# 03_-_ETHERNET.net
KiCad netlist of a schematic drawn in Altium Designer
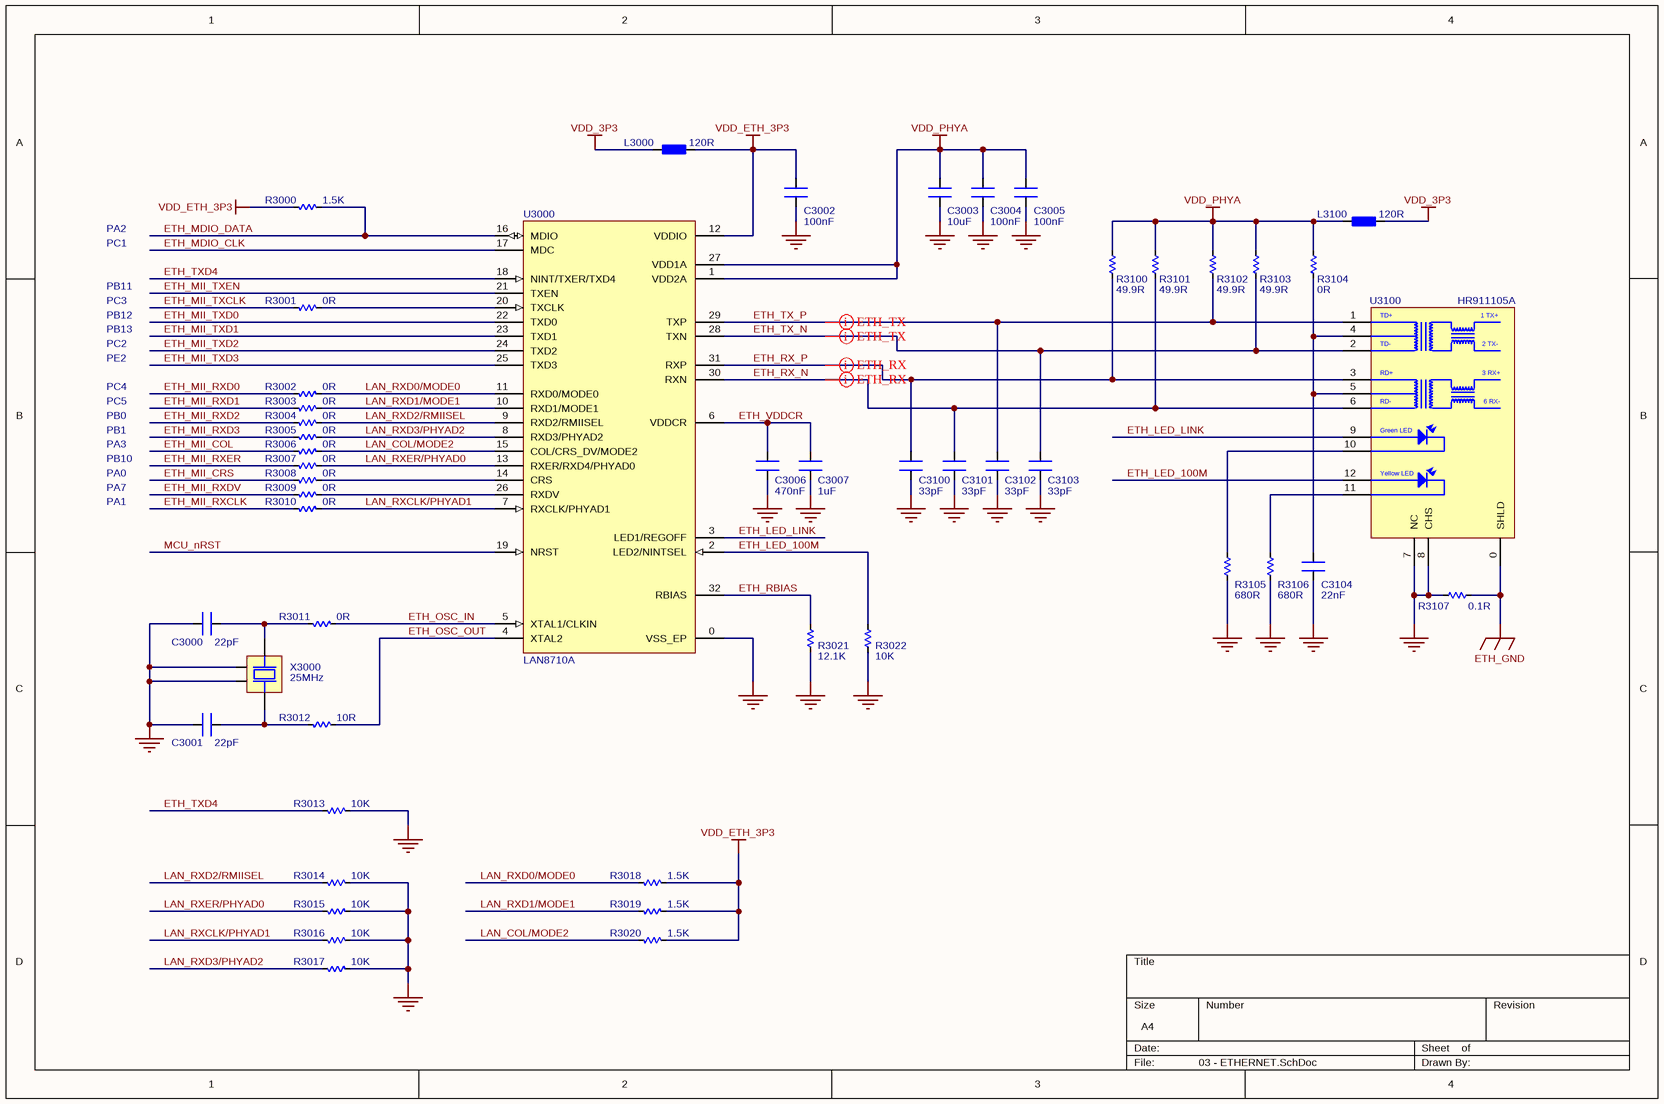
[diagram p0: 03 - ETHERNET.SchDoc]

(export (version "E")
  (design (tool "Eeschema 10.0.6"))
  (components
    (comp (ref "C3000")
      (value "22pF")
      (footprint "CN-SMD-0402")
      (description "Ceramic Capacitor SMD 0402 22pF ±20% 50V")
      (fields (field (name "Comment") "Capacitor"))
      (libsource (lib "AS50") (part "Cap"))
    )
    (comp (ref "C3001")
      (value "22pF")
      (footprint "CN-SMD-0402")
      (description "Ceramic Capacitor SMD 0402 22pF ±20% 50V")
      (fields (field (name "Comment") "Capacitor"))
      (libsource (lib "AS50") (part "Cap"))
    )
    (comp (ref "C3002")
      (value "100nF")
      (footprint "CN-SMD-0402")
      (description "Ceramic Capacitor SMD 0402 100nF ±20% 16V")
      (fields (field (name "Comment") "Capacitor"))
      (libsource (lib "AS50") (part "Cap"))
    )
    (comp (ref "C3003")
      (value "10uF")
      (footprint "CN-SMD-0603")
      (description "Ceramic Capacitor SMD 0603 10uF ±20% 10V")
      (fields (field (name "Comment") "Capacitor"))
      (libsource (lib "AS50") (part "Cap"))
    )
    (comp (ref "C3004")
      (value "100nF")
      (footprint "CN-SMD-0402")
      (description "Ceramic Capacitor SMD 0402 100nF ±20% 16V")
      (fields (field (name "Comment") "Capacitor"))
      (libsource (lib "AS50") (part "Cap"))
    )
    (comp (ref "C3005")
      (value "100nF")
      (footprint "CN-SMD-0402")
      (description "Ceramic Capacitor SMD 0402 100nF ±20% 16V")
      (fields (field (name "Comment") "Capacitor"))
      (libsource (lib "AS50") (part "Cap"))
    )
    (comp (ref "C3006")
      (value "470nF")
      (footprint "CN-SMD-0402")
      (description "Ceramic Capacitor SMD 0402 470nF ±20% 10V")
      (fields (field (name "Comment") "Capacitor"))
      (libsource (lib "AS50") (part "Cap"))
    )
    (comp (ref "C3007")
      (value "1uF")
      (footprint "CN-SMD-0603")
      (description "Ceramic Capacitor SMD 0603 1uF ±20% 50V")
      (fields (field (name "Comment") "Capacitor"))
      (libsource (lib "AS50") (part "Cap"))
    )
    (comp (ref "C3100")
      (value "33pF")
      (footprint "CN-SMD-0402")
      (description "Ceramic Capacitor SMD 0402 33pF ±20% 50V")
      (fields (field (name "Comment") "Capacitor"))
      (libsource (lib "AS50") (part "Cap"))
    )
    (comp (ref "C3101")
      (value "33pF")
      (footprint "CN-SMD-0402")
      (description "Ceramic Capacitor SMD 0402 33pF ±20% 50V")
      (fields (field (name "Comment") "Capacitor"))
      (libsource (lib "AS50") (part "Cap"))
    )
    (comp (ref "C3102")
      (value "33pF")
      (footprint "CN-SMD-0402")
      (description "Ceramic Capacitor SMD 0402 33pF ±20% 50V")
      (fields (field (name "Comment") "Capacitor"))
      (libsource (lib "AS50") (part "Cap"))
    )
    (comp (ref "C3103")
      (value "33pF")
      (footprint "CN-SMD-0402")
      (description "Ceramic Capacitor SMD 0402 33pF ±20% 50V")
      (fields (field (name "Comment") "Capacitor"))
      (libsource (lib "AS50") (part "Cap"))
    )
    (comp (ref "C3104")
      (value "22nF")
      (footprint "CN-SMD-0402")
      (description "Ceramic Capacitor SMD 0402 22nF ±20% 50V")
      (fields (field (name "Comment") "Capacitor"))
      (libsource (lib "AS50") (part "Cap"))
    )
    (comp (ref "L3000")
      (value "120R")
      (footprint "L-SMD-0603")
      (description "Ferrite bead SMD 0603 120 Ohm @100MHz")
      (fields (field (name "Comment") "Ferrite bead"))
      (libsource (lib "AS50") (part "Ferrite bead"))
    )
    (comp (ref "L3100")
      (value "120R")
      (footprint "L-SMD-0603")
      (description "Ferrite bead SMD 0603 120 Ohm @100MHz")
      (fields (field (name "Comment") "Ferrite bead"))
      (libsource (lib "AS50") (part "Ferrite bead"))
    )
    (comp (ref "R3000")
      (value "1.5K")
      (footprint "RES-SMD-0402")
      (description "Resistor SMD 0402 1.5K 1% 0.063W")
      (fields (field (name "Comment") "Resistor"))
      (libsource (lib "AS50") (part "Res"))
    )
    (comp (ref "R3001")
      (value "0R")
      (footprint "RES-SMD-0402")
      (description "Resistor SMD 0402 0R 1% 0.063W")
      (fields (field (name "Comment") "Resistor"))
      (libsource (lib "AS50") (part "Res"))
    )
    (comp (ref "R3002")
      (value "0R")
      (footprint "RES-SMD-0402")
      (description "Resistor SMD 0402 0R 1% 0.063W")
      (fields (field (name "Comment") "Resistor"))
      (libsource (lib "AS50") (part "Res"))
    )
    (comp (ref "R3003")
      (value "0R")
      (footprint "RES-SMD-0402")
      (description "Resistor SMD 0402 0R 1% 0.063W")
      (fields (field (name "Comment") "Resistor"))
      (libsource (lib "AS50") (part "Res"))
    )
    (comp (ref "R3004")
      (value "0R")
      (footprint "RES-SMD-0402")
      (description "Resistor SMD 0402 0R 1% 0.063W")
      (fields (field (name "Comment") "Resistor"))
      (libsource (lib "AS50") (part "Res"))
    )
    (comp (ref "R3005")
      (value "0R")
      (footprint "RES-SMD-0402")
      (description "Resistor SMD 0402 0R 1% 0.063W")
      (fields (field (name "Comment") "Resistor"))
      (libsource (lib "AS50") (part "Res"))
    )
    (comp (ref "R3006")
      (value "0R")
      (footprint "RES-SMD-0402")
      (description "Resistor SMD 0402 0R 1% 0.063W")
      (fields (field (name "Comment") "Resistor"))
      (libsource (lib "AS50") (part "Res"))
    )
    (comp (ref "R3007")
      (value "0R")
      (footprint "RES-SMD-0402")
      (description "Resistor SMD 0402 0R 1% 0.063W")
      (fields (field (name "Comment") "Resistor"))
      (libsource (lib "AS50") (part "Res"))
    )
    (comp (ref "R3008")
      (value "0R")
      (footprint "RES-SMD-0402")
      (description "Resistor SMD 0402 0R 1% 0.063W")
      (fields (field (name "Comment") "Resistor"))
      (libsource (lib "AS50") (part "Res"))
    )
    (comp (ref "R3009")
      (value "0R")
      (footprint "RES-SMD-0402")
      (description "Resistor SMD 0402 0R 1% 0.063W")
      (fields (field (name "Comment") "Resistor"))
      (libsource (lib "AS50") (part "Res"))
    )
    (comp (ref "R3010")
      (value "0R")
      (footprint "RES-SMD-0402")
      (description "Resistor SMD 0402 0R 1% 0.063W")
      (fields (field (name "Comment") "Resistor"))
      (libsource (lib "AS50") (part "Res"))
    )
    (comp (ref "R3011")
      (value "0R")
      (footprint "RES-SMD-0402")
      (description "Resistor SMD 0402 0R 1% 0.063W")
      (fields (field (name "Comment") "Resistor"))
      (libsource (lib "AS50") (part "Res"))
    )
    (comp (ref "R3012")
      (value "10R")
      (footprint "RES-SMD-0402")
      (description "Resistor SMD 0402 10R 1% 0.063W")
      (fields (field (name "Comment") "Resistor"))
      (libsource (lib "AS50") (part "Res"))
    )
    (comp (ref "R3013")
      (value "10K")
      (footprint "RES-SMD-0402")
      (description "Resistor SMD 0402 10K 1% 0.063W")
      (fields (field (name "Comment") "Resistor"))
      (libsource (lib "AS50") (part "Res"))
    )
    (comp (ref "R3014")
      (value "10K")
      (footprint "RES-SMD-0402")
      (description "Resistor SMD 0402 10K 1% 0.063W")
      (fields (field (name "Comment") "Resistor"))
      (libsource (lib "AS50") (part "Res"))
    )
    (comp (ref "R3015")
      (value "10K")
      (footprint "RES-SMD-0402")
      (description "Resistor SMD 0402 10K 1% 0.063W")
      (fields (field (name "Comment") "Resistor"))
      (libsource (lib "AS50") (part "Res"))
    )
    (comp (ref "R3016")
      (value "10K")
      (footprint "RES-SMD-0402")
      (description "Resistor SMD 0402 10K 1% 0.063W")
      (fields (field (name "Comment") "Resistor"))
      (libsource (lib "AS50") (part "Res"))
    )
    (comp (ref "R3017")
      (value "10K")
      (footprint "RES-SMD-0402")
      (description "Resistor SMD 0402 10K 1% 0.063W")
      (fields (field (name "Comment") "Resistor"))
      (libsource (lib "AS50") (part "Res"))
    )
    (comp (ref "R3018")
      (value "1.5K")
      (footprint "RES-SMD-0402")
      (description "Resistor SMD 0402 1.5K 1% 0.063W")
      (fields (field (name "Comment") "Resistor"))
      (libsource (lib "AS50") (part "Res"))
    )
    (comp (ref "R3019")
      (value "1.5K")
      (footprint "RES-SMD-0402")
      (description "Resistor SMD 0402 1.5K 1% 0.063W")
      (fields (field (name "Comment") "Resistor"))
      (libsource (lib "AS50") (part "Res"))
    )
    (comp (ref "R3020")
      (value "1.5K")
      (footprint "RES-SMD-0402")
      (description "Resistor SMD 0402 1.5K 1% 0.063W")
      (fields (field (name "Comment") "Resistor"))
      (libsource (lib "AS50") (part "Res"))
    )
    (comp (ref "R3021")
      (value "12.1K")
      (footprint "RES-SMD-0402")
      (description "Resistor SMD 0402 12.1K 1% 0.063W")
      (fields (field (name "Comment") "Resistor"))
      (libsource (lib "AS50") (part "Res"))
    )
    (comp (ref "R3022")
      (value "10K")
      (footprint "RES-SMD-0402")
      (description "Resistor SMD 0402 10K 1% 0.063W")
      (fields (field (name "Comment") "Resistor"))
      (libsource (lib "AS50") (part "Res"))
    )
    (comp (ref "R3100")
      (value "49.9R")
      (footprint "RES-SMD-0402")
      (description "Resistor SMD 0402 49.9R 1% 0.063W")
      (fields (field (name "Comment") "Resistor"))
      (libsource (lib "AS50") (part "Res"))
    )
    (comp (ref "R3101")
      (value "49.9R")
      (footprint "RES-SMD-0402")
      (description "Resistor SMD 0402 49.9R 1% 0.063W")
      (fields (field (name "Comment") "Resistor"))
      (libsource (lib "AS50") (part "Res"))
    )
    (comp (ref "R3102")
      (value "49.9R")
      (footprint "RES-SMD-0402")
      (description "Resistor SMD 0402 49.9R 1% 0.063W")
      (fields (field (name "Comment") "Resistor"))
      (libsource (lib "AS50") (part "Res"))
    )
    (comp (ref "R3103")
      (value "49.9R")
      (footprint "RES-SMD-0402")
      (description "Resistor SMD 0402 49.9R 1% 0.063W")
      (fields (field (name "Comment") "Resistor"))
      (libsource (lib "AS50") (part "Res"))
    )
    (comp (ref "R3104")
      (value "0R")
      (footprint "RES-SMD-0402")
      (description "Resistor SMD 0402 0R 1% 0.063W")
      (fields (field (name "Comment") "Resistor"))
      (libsource (lib "AS50") (part "Res"))
    )
    (comp (ref "R3105")
      (value "680R")
      (footprint "RES-SMD-0402")
      (description "Resistor SMD 0402 680R 1% 0.063W")
      (fields (field (name "Comment") "Resistor"))
      (libsource (lib "AS50") (part "Res"))
    )
    (comp (ref "R3106")
      (value "680R")
      (footprint "RES-SMD-0402")
      (description "Resistor SMD 0402 680R 1% 0.063W")
      (fields (field (name "Comment") "Resistor"))
      (libsource (lib "AS50") (part "Res"))
    )
    (comp (ref "R3107")
      (value "0.1R")
      (footprint "RES-SMD-1206")
      (description "Resistor SMD 1206 0.1R 1% 0.25W")
      (fields (field (name "Comment") "Resistor"))
      (libsource (lib "AS50") (part "Res"))
    )
    (comp (ref "U3000")
      (value "LAN8710A")
      (footprint "IC:QFN50P500X500X100-33N-D")
      (description "Microchip MII/RMII 10/100 Ethernet Transceiver\r\nwith HP Auto-MDIX and flexPWR® Technology")
      (fields
        (field (name "MANUFACTURER_PART_NUMBER") "LAN8710AI-EZK")
        (field (name "MOUSER PART NUMBER") "886-LAN8710AI-EZK")
      )
      (libsource (lib "AS50") (part "LAN8710A"))
    )
    (comp (ref "U3100")
      (value "HR911105A")
      (footprint "RJ-45_HR911105A")
      (libsource (lib "AS50") (part "HR911105A"))
    )
    (comp (ref "X3000")
      (value "25MHz")
      (footprint "XT-SMD-3225-4P")
      (description "Crystal Oscillator SMD-3225 25MHz 4-pin")
      (fields (field (name "Comment") "Crystal"))
      (libsource (lib "AS50") (part "XT4"))
    )
  )
  (nets
    (net (code "1") (name "/ETH_LED_100M") (class "Default")
      (node (ref "R3022") (pin "1") (pinfunction "1_1") (pintype "passive"))
      (node (ref "U3000") (pin "2") (pinfunction "LED2/NINTSEL_2") (pintype "input"))
      (node (ref "U3100") (pin "12") (pinfunction "Yellow+_12") (pintype "passive"))
    )
    (net (code "2") (name "/ETH_LED_LINK") (class "Default")
      (node (ref "U3000") (pin "3") (pinfunction "LED1/REGOFF_3") (pintype "passive"))
      (node (ref "U3100") (pin "9") (pinfunction "Green+_9") (pintype "passive"))
    )
    (net (code "3") (name "/ETH_MDIO_CLK") (class "Default")
      (node (ref "U3000") (pin "17") (pinfunction "MDC_17") (pintype "passive"))
    )
    (net (code "4") (name "/ETH_MDIO_DATA") (class "Default")
      (node (ref "R3000") (pin "1") (pinfunction "1_1") (pintype "passive"))
      (node (ref "U3000") (pin "16") (pinfunction "MDIO_16") (pintype "bidirectional"))
    )
    (net (code "5") (name "/ETH_MII_COL") (class "Default")
      (node (ref "R3006") (pin "2") (pinfunction "2_2") (pintype "passive"))
    )
    (net (code "6") (name "/ETH_MII_CRS") (class "Default")
      (node (ref "R3008") (pin "2") (pinfunction "2_2") (pintype "passive"))
    )
    (net (code "7") (name "/ETH_MII_RXCLK") (class "Default")
      (node (ref "R3010") (pin "2") (pinfunction "2_2") (pintype "passive"))
    )
    (net (code "8") (name "/ETH_MII_RXD0") (class "Default")
      (node (ref "R3002") (pin "2") (pinfunction "2_2") (pintype "passive"))
    )
    (net (code "9") (name "/ETH_MII_RXD1") (class "Default")
      (node (ref "R3003") (pin "2") (pinfunction "2_2") (pintype "passive"))
    )
    (net (code "10") (name "/ETH_MII_RXD2") (class "Default")
      (node (ref "R3004") (pin "2") (pinfunction "2_2") (pintype "passive"))
    )
    (net (code "11") (name "/ETH_MII_RXD3") (class "Default")
      (node (ref "R3005") (pin "2") (pinfunction "2_2") (pintype "passive"))
    )
    (net (code "12") (name "/ETH_MII_RXDV") (class "Default")
      (node (ref "R3009") (pin "2") (pinfunction "2_2") (pintype "passive"))
    )
    (net (code "13") (name "/ETH_MII_RXER") (class "Default")
      (node (ref "R3007") (pin "2") (pinfunction "2_2") (pintype "passive"))
    )
    (net (code "14") (name "/ETH_MII_TXCLK") (class "Default")
      (node (ref "R3001") (pin "2") (pinfunction "2_2") (pintype "passive"))
    )
    (net (code "15") (name "/ETH_MII_TXD0") (class "Default")
      (node (ref "U3000") (pin "22") (pinfunction "TXD0_22") (pintype "passive"))
    )
    (net (code "16") (name "/ETH_MII_TXD1") (class "Default")
      (node (ref "U3000") (pin "23") (pinfunction "TXD1_23") (pintype "passive"))
    )
    (net (code "17") (name "/ETH_MII_TXD2") (class "Default")
      (node (ref "U3000") (pin "24") (pinfunction "TXD2_24") (pintype "passive"))
    )
    (net (code "18") (name "/ETH_MII_TXD3") (class "Default")
      (node (ref "U3000") (pin "25") (pinfunction "TXD3_25") (pintype "passive"))
    )
    (net (code "19") (name "/ETH_MII_TXEN") (class "Default")
      (node (ref "U3000") (pin "21") (pinfunction "TXEN_21") (pintype "passive"))
    )
    (net (code "20") (name "/ETH_OSC_IN") (class "Default")
      (node (ref "R3011") (pin "1") (pinfunction "1_1") (pintype "passive"))
      (node (ref "U3000") (pin "5") (pinfunction "XTAL1/CLKIN_5") (pintype "input"))
    )
    (net (code "21") (name "/ETH_OSC_OUT") (class "Default")
      (node (ref "R3012") (pin "1") (pinfunction "1_1") (pintype "passive"))
      (node (ref "U3000") (pin "4") (pinfunction "XTAL2_4") (pintype "passive"))
    )
    (net (code "22") (name "/ETH_RBIAS") (class "Default")
      (node (ref "R3021") (pin "2") (pinfunction "2_2") (pintype "passive"))
      (node (ref "U3000") (pin "32") (pinfunction "RBIAS_32") (pintype "passive"))
    )
    (net (code "23") (name "/ETH_RX_N") (class "Default")
      (node (ref "C3101") (pin "2") (pinfunction "2_2") (pintype "passive"))
      (node (ref "R3101") (pin "2") (pinfunction "2_2") (pintype "passive"))
      (node (ref "U3000") (pin "30") (pinfunction "RXN_30") (pintype "passive"))
      (node (ref "U3100") (pin "6") (pinfunction "RD-_6") (pintype "passive"))
    )
    (net (code "24") (name "/ETH_RX_P") (class "Default")
      (node (ref "C3100") (pin "2") (pinfunction "2_2") (pintype "passive"))
      (node (ref "R3100") (pin "2") (pinfunction "2_2") (pintype "passive"))
      (node (ref "U3000") (pin "31") (pinfunction "RXP_31") (pintype "passive"))
      (node (ref "U3100") (pin "3") (pinfunction "RD+_3") (pintype "passive"))
    )
    (net (code "25") (name "/ETH_TXD4") (class "Default")
      (node (ref "R3013") (pin "2") (pinfunction "2_2") (pintype "passive"))
      (node (ref "U3000") (pin "18") (pinfunction "NINT/TXER/TXD4_18") (pintype "input"))
    )
    (net (code "26") (name "/ETH_TX_N") (class "Default")
      (node (ref "C3103") (pin "2") (pinfunction "2_2") (pintype "passive"))
      (node (ref "R3103") (pin "2") (pinfunction "2_2") (pintype "passive"))
      (node (ref "U3000") (pin "28") (pinfunction "TXN_28") (pintype "passive"))
      (node (ref "U3100") (pin "2") (pinfunction "TD-_2") (pintype "passive"))
    )
    (net (code "27") (name "/ETH_TX_P") (class "Default")
      (node (ref "C3102") (pin "2") (pinfunction "2_2") (pintype "passive"))
      (node (ref "R3102") (pin "2") (pinfunction "2_2") (pintype "passive"))
      (node (ref "U3000") (pin "29") (pinfunction "TXP_29") (pintype "passive"))
      (node (ref "U3100") (pin "1") (pinfunction "TD+_1") (pintype "passive"))
    )
    (net (code "28") (name "/ETH_VDDCR") (class "Default")
      (node (ref "C3006") (pin "2") (pinfunction "2_2") (pintype "passive"))
      (node (ref "C3007") (pin "2") (pinfunction "2_2") (pintype "passive"))
      (node (ref "U3000") (pin "6") (pinfunction "VDDCR_6") (pintype "power_in"))
    )
    (net (code "29") (name "/LAN_COL{slash}MODE2") (class "Default")
      (node (ref "R3006") (pin "1") (pinfunction "1_1") (pintype "passive"))
      (node (ref "R3020") (pin "2") (pinfunction "2_2") (pintype "passive"))
      (node (ref "U3000") (pin "15") (pinfunction "COL/CRS_DV/MODE2_15") (pintype "passive"))
    )
    (net (code "30") (name "/LAN_RXCLK{slash}PHYAD1") (class "Default")
      (node (ref "R3010") (pin "1") (pinfunction "1_1") (pintype "passive"))
      (node (ref "R3016") (pin "2") (pinfunction "2_2") (pintype "passive"))
      (node (ref "U3000") (pin "7") (pinfunction "RXCLK/PHYAD1_7") (pintype "input"))
    )
    (net (code "31") (name "/LAN_RXD0{slash}MODE0") (class "Default")
      (node (ref "R3002") (pin "1") (pinfunction "1_1") (pintype "passive"))
      (node (ref "R3018") (pin "2") (pinfunction "2_2") (pintype "passive"))
      (node (ref "U3000") (pin "11") (pinfunction "RXD0/MODE0_11") (pintype "passive"))
    )
    (net (code "32") (name "/LAN_RXD1{slash}MODE1") (class "Default")
      (node (ref "R3003") (pin "1") (pinfunction "1_1") (pintype "passive"))
      (node (ref "R3019") (pin "2") (pinfunction "2_2") (pintype "passive"))
      (node (ref "U3000") (pin "10") (pinfunction "RXD1/MODE1_10") (pintype "passive"))
    )
    (net (code "33") (name "/LAN_RXD2{slash}RMIISEL") (class "Default")
      (node (ref "R3004") (pin "1") (pinfunction "1_1") (pintype "passive"))
      (node (ref "R3014") (pin "2") (pinfunction "2_2") (pintype "passive"))
      (node (ref "U3000") (pin "9") (pinfunction "RXD2/RMIISEL_9") (pintype "passive"))
    )
    (net (code "34") (name "/LAN_RXD3{slash}PHYAD2") (class "Default")
      (node (ref "R3005") (pin "1") (pinfunction "1_1") (pintype "passive"))
      (node (ref "R3017") (pin "2") (pinfunction "2_2") (pintype "passive"))
      (node (ref "U3000") (pin "8") (pinfunction "RXD3/PHYAD2_8") (pintype "passive"))
    )
    (net (code "35") (name "/LAN_RXER{slash}PHYAD0") (class "Default")
      (node (ref "R3007") (pin "1") (pinfunction "1_1") (pintype "passive"))
      (node (ref "R3015") (pin "2") (pinfunction "2_2") (pintype "passive"))
      (node (ref "U3000") (pin "13") (pinfunction "RXER/RXD4/PHYAD0_13") (pintype "passive"))
    )
    (net (code "36") (name "/MCU_nRST") (class "Default")
      (node (ref "U3000") (pin "19") (pinfunction "NRST_19") (pintype "input"))
    )
    (net (code "37") (name "ETH_GND") (class "Default")
      (node (ref "R3107") (pin "2") (pinfunction "2_2") (pintype "passive"))
      (node (ref "U3100") (pin "0") (pinfunction "SHLD_0") (pintype "passive"))
    )
    (net (code "38") (name "GND") (class "Default")
      (node (ref "C3000") (pin "2") (pinfunction "2_2") (pintype "passive"))
      (node (ref "C3001") (pin "2") (pinfunction "2_2") (pintype "passive"))
      (node (ref "C3002") (pin "1") (pinfunction "1_1") (pintype "passive"))
      (node (ref "C3003") (pin "1") (pinfunction "1_1") (pintype "passive"))
      (node (ref "C3004") (pin "1") (pinfunction "1_1") (pintype "passive"))
      (node (ref "C3005") (pin "1") (pinfunction "1_1") (pintype "passive"))
      (node (ref "C3006") (pin "1") (pinfunction "1_1") (pintype "passive"))
      (node (ref "C3007") (pin "1") (pinfunction "1_1") (pintype "passive"))
      (node (ref "C3100") (pin "1") (pinfunction "1_1") (pintype "passive"))
      (node (ref "C3101") (pin "1") (pinfunction "1_1") (pintype "passive"))
      (node (ref "C3102") (pin "1") (pinfunction "1_1") (pintype "passive"))
      (node (ref "C3103") (pin "1") (pinfunction "1_1") (pintype "passive"))
      (node (ref "C3104") (pin "1") (pinfunction "1_1") (pintype "passive"))
      (node (ref "R3013") (pin "1") (pinfunction "1_1") (pintype "passive"))
      (node (ref "R3014") (pin "1") (pinfunction "1_1") (pintype "passive"))
      (node (ref "R3015") (pin "1") (pinfunction "1_1") (pintype "passive"))
      (node (ref "R3016") (pin "1") (pinfunction "1_1") (pintype "passive"))
      (node (ref "R3017") (pin "1") (pinfunction "1_1") (pintype "passive"))
      (node (ref "R3021") (pin "1") (pinfunction "1_1") (pintype "passive"))
      (node (ref "R3022") (pin "2") (pinfunction "2_2") (pintype "passive"))
      (node (ref "R3105") (pin "2") (pinfunction "2_2") (pintype "passive"))
      (node (ref "R3106") (pin "2") (pinfunction "2_2") (pintype "passive"))
      (node (ref "R3107") (pin "1") (pinfunction "1_1") (pintype "passive"))
      (node (ref "U3000") (pin "0") (pinfunction "VSS_EP_0") (pintype "power_in"))
      (node (ref "U3100") (pin "7") (pinfunction "NC_7") (pintype "passive"))
      (node (ref "U3100") (pin "8") (pinfunction "CHS_8") (pintype "passive"))
      (node (ref "X3000") (pin "2") (pinfunction "2_2") (pintype "power_in"))
      (node (ref "X3000") (pin "4") (pinfunction "4_4") (pintype "power_in"))
    )
    (net (code "39") (name "Net-(C3000-Pad1)") (class "Default")
      (node (ref "C3000") (pin "1") (pinfunction "1_1") (pintype "passive"))
      (node (ref "R3011") (pin "2") (pinfunction "2_2") (pintype "passive"))
      (node (ref "X3000") (pin "3") (pinfunction "3_3") (pintype "passive"))
    )
    (net (code "40") (name "Net-(C3001-Pad1)") (class "Default")
      (node (ref "C3001") (pin "1") (pinfunction "1_1") (pintype "passive"))
      (node (ref "R3012") (pin "2") (pinfunction "2_2") (pintype "passive"))
      (node (ref "X3000") (pin "1") (pinfunction "1_1") (pintype "passive"))
    )
    (net (code "41") (name "Net-(C3104-Pad2)") (class "Default")
      (node (ref "C3104") (pin "2") (pinfunction "2_2") (pintype "passive"))
      (node (ref "R3104") (pin "2") (pinfunction "2_2") (pintype "passive"))
      (node (ref "U3100") (pin "4") (pinfunction "2,5V_4") (pintype "passive"))
      (node (ref "U3100") (pin "5") (pinfunction "2,5V_5") (pintype "passive"))
    )
    (net (code "42") (name "Net-(U3000-CRS)") (class "Default")
      (node (ref "R3008") (pin "1") (pinfunction "1_1") (pintype "passive"))
      (node (ref "U3000") (pin "14") (pinfunction "CRS_14") (pintype "passive"))
    )
    (net (code "43") (name "Net-(U3000-RXDV)") (class "Default")
      (node (ref "R3009") (pin "1") (pinfunction "1_1") (pintype "passive"))
      (node (ref "U3000") (pin "26") (pinfunction "RXDV_26") (pintype "passive"))
    )
    (net (code "44") (name "Net-(U3000-TXCLK)") (class "Default")
      (node (ref "R3001") (pin "1") (pinfunction "1_1") (pintype "passive"))
      (node (ref "U3000") (pin "20") (pinfunction "TXCLK_20") (pintype "input"))
    )
    (net (code "45") (name "Net-(U3100-Green-)") (class "Default")
      (node (ref "R3105") (pin "1") (pinfunction "1_1") (pintype "passive"))
      (node (ref "U3100") (pin "10") (pinfunction "Green-_10") (pintype "passive"))
    )
    (net (code "46") (name "Net-(U3100-Yellow-)") (class "Default")
      (node (ref "R3106") (pin "1") (pinfunction "1_1") (pintype "passive"))
      (node (ref "U3100") (pin "11") (pinfunction "Yellow-_11") (pintype "passive"))
    )
    (net (code "47") (name "VDD_3P3") (class "Default")
      (node (ref "L3000") (pin "2") (pinfunction "2_2") (pintype "passive"))
      (node (ref "L3100") (pin "1") (pinfunction "1_1") (pintype "passive"))
    )
    (net (code "48") (name "VDD_ETH_3P3") (class "Default")
      (node (ref "C3002") (pin "2") (pinfunction "2_2") (pintype "passive"))
      (node (ref "L3000") (pin "1") (pinfunction "1_1") (pintype "passive"))
      (node (ref "R3000") (pin "2") (pinfunction "2_2") (pintype "passive"))
      (node (ref "R3018") (pin "1") (pinfunction "1_1") (pintype "passive"))
      (node (ref "R3019") (pin "1") (pinfunction "1_1") (pintype "passive"))
      (node (ref "R3020") (pin "1") (pinfunction "1_1") (pintype "passive"))
      (node (ref "U3000") (pin "12") (pinfunction "VDDIO_12") (pintype "power_in"))
    )
    (net (code "49") (name "VDD_PHYA") (class "Default")
      (node (ref "C3003") (pin "2") (pinfunction "2_2") (pintype "passive"))
      (node (ref "C3004") (pin "2") (pinfunction "2_2") (pintype "passive"))
      (node (ref "C3005") (pin "2") (pinfunction "2_2") (pintype "passive"))
      (node (ref "L3100") (pin "2") (pinfunction "2_2") (pintype "passive"))
      (node (ref "R3100") (pin "1") (pinfunction "1_1") (pintype "passive"))
      (node (ref "R3101") (pin "1") (pinfunction "1_1") (pintype "passive"))
      (node (ref "R3102") (pin "1") (pinfunction "1_1") (pintype "passive"))
      (node (ref "R3103") (pin "1") (pinfunction "1_1") (pintype "passive"))
      (node (ref "R3104") (pin "1") (pinfunction "1_1") (pintype "passive"))
      (node (ref "U3000") (pin "1") (pinfunction "VDD2A_1") (pintype "power_in"))
      (node (ref "U3000") (pin "27") (pinfunction "VDD1A_27") (pintype "power_in"))
    )
  )
)
